# MPU6050.net
KiCad netlist of a schematic drawn in Altium Designer
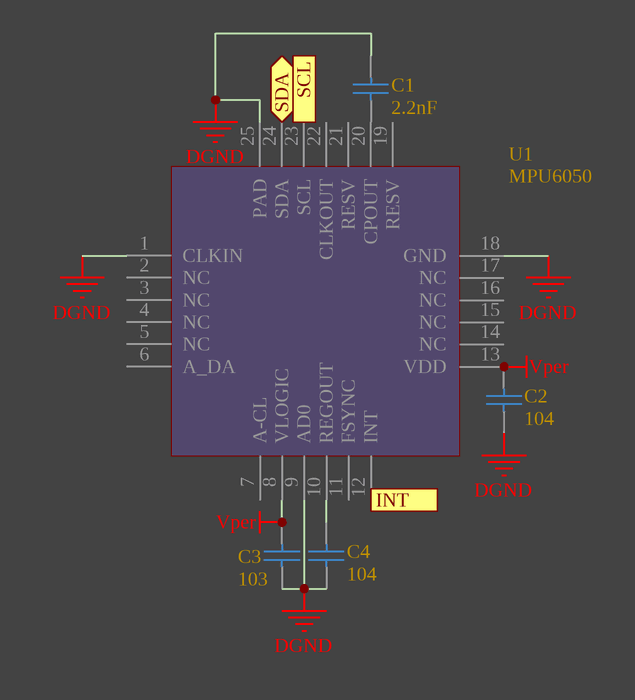
[diagram p0: MPU6050.SchDoc]

(export (version "E")
  (design (tool "Eeschema 10.0.6"))
  (components
    (comp (ref "C1")
      (value "2.2nF")
      (footprint "C0402")
      (description "Capacitor")
      (fields (field (name "PUBLISHER") "Altium Limited"))
      (libsource (lib "iMag") (part "电容"))
    )
    (comp (ref "C2")
      (value "104")
      (footprint "C0402")
      (description "Capacitor")
      (fields (field (name "PUBLISHER") "Altium Limited"))
      (libsource (lib "iMag") (part "电容"))
    )
    (comp (ref "C3")
      (value "103")
      (footprint "C0402")
      (description "Capacitor")
      (fields (field (name "PUBLISHER") "Altium Limited"))
      (libsource (lib "iMag") (part "电容"))
    )
    (comp (ref "C4")
      (value "104")
      (footprint "C0402")
      (description "Capacitor")
      (fields (field (name "PUBLISHER") "Altium Limited"))
      (libsource (lib "iMag") (part "电容"))
    )
    (comp (ref "U1") (value "MPU6050") (footprint "QFN-24_4x4x05P") (libsource (lib "iMag") (part "MPU6050")))
  )
  (nets
    (net (code "1") (name "/INT") (class "Default")
      (node (ref "U1") (pin "12") (pinfunction "INT_12") (pintype "passive"))
    )
    (net (code "2") (name "/SCL") (class "Default")
      (node (ref "U1") (pin "23") (pinfunction "SCL_23") (pintype "passive"))
    )
    (net (code "3") (name "/SDA") (class "Default")
      (node (ref "U1") (pin "24") (pinfunction "SDA_24") (pintype "passive"))
    )
    (net (code "4") (name "DGND") (class "Default")
      (node (ref "C1") (pin "2") (pinfunction "2_2") (pintype "passive"))
      (node (ref "C2") (pin "1") (pinfunction "1_1") (pintype "passive"))
      (node (ref "C3") (pin "1") (pinfunction "1_1") (pintype "passive"))
      (node (ref "C4") (pin "1") (pinfunction "1_1") (pintype "passive"))
      (node (ref "U1") (pin "1") (pinfunction "CLKIN_1") (pintype "passive"))
      (node (ref "U1") (pin "18") (pinfunction "GND_18") (pintype "passive"))
      (node (ref "U1") (pin "25") (pinfunction "PAD_25") (pintype "passive"))
      (node (ref "U1") (pin "9") (pinfunction "AD0_9") (pintype "passive"))
    )
    (net (code "5") (name "Net-(U1-CPOUT)") (class "Default")
      (node (ref "C1") (pin "1") (pinfunction "1_1") (pintype "passive"))
      (node (ref "U1") (pin "20") (pinfunction "CPOUT_20") (pintype "passive"))
    )
    (net (code "6") (name "Net-(U1-REGOUT)") (class "Default")
      (node (ref "C4") (pin "2") (pinfunction "2_2") (pintype "passive"))
      (node (ref "U1") (pin "10") (pinfunction "REGOUT_10") (pintype "passive"))
    )
    (net (code "7") (name "Vper") (class "Default")
      (node (ref "C2") (pin "2") (pinfunction "2_2") (pintype "passive"))
      (node (ref "C3") (pin "2") (pinfunction "2_2") (pintype "passive"))
      (node (ref "U1") (pin "13") (pinfunction "VDD_13") (pintype "passive"))
      (node (ref "U1") (pin "8") (pinfunction "VLOGIC_8") (pintype "passive"))
    )
    (net (code "8") (name "unconnected-(U1-A-CL-Pad7)") (class "Default")
      (node (ref "U1") (pin "7") (pinfunction "A-CL_7") (pintype "passive"))
    )
    (net (code "9") (name "unconnected-(U1-A_DA-Pad6)") (class "Default")
      (node (ref "U1") (pin "6") (pinfunction "A_DA_6") (pintype "passive"))
    )
    (net (code "10") (name "unconnected-(U1-CLKOUT-Pad22)") (class "Default")
      (node (ref "U1") (pin "22") (pinfunction "CLKOUT_22") (pintype "passive"))
    )
    (net (code "11") (name "unconnected-(U1-FSYNC-Pad11)") (class "Default")
      (node (ref "U1") (pin "11") (pinfunction "FSYNC_11") (pintype "passive"))
    )
    (net (code "12") (name "unconnected-(U1-NC-Pad2)") (class "Default")
      (node (ref "U1") (pin "2") (pinfunction "NC_2") (pintype "passive"))
    )
    (net (code "13") (name "unconnected-(U1-NC-Pad3)") (class "Default")
      (node (ref "U1") (pin "3") (pinfunction "NC_3") (pintype "passive"))
    )
    (net (code "14") (name "unconnected-(U1-NC-Pad4)") (class "Default")
      (node (ref "U1") (pin "4") (pinfunction "NC_4") (pintype "passive"))
    )
    (net (code "15") (name "unconnected-(U1-NC-Pad5)") (class "Default")
      (node (ref "U1") (pin "5") (pinfunction "NC_5") (pintype "passive"))
    )
    (net (code "16") (name "unconnected-(U1-NC-Pad14)") (class "Default")
      (node (ref "U1") (pin "14") (pinfunction "NC_14") (pintype "passive"))
    )
    (net (code "17") (name "unconnected-(U1-NC-Pad15)") (class "Default")
      (node (ref "U1") (pin "15") (pinfunction "NC_15") (pintype "passive"))
    )
    (net (code "18") (name "unconnected-(U1-NC-Pad16)") (class "Default")
      (node (ref "U1") (pin "16") (pinfunction "NC_16") (pintype "passive"))
    )
    (net (code "19") (name "unconnected-(U1-NC-Pad17)") (class "Default")
      (node (ref "U1") (pin "17") (pinfunction "NC_17") (pintype "passive"))
    )
    (net (code "20") (name "unconnected-(U1-RESV-Pad19)") (class "Default")
      (node (ref "U1") (pin "19") (pinfunction "RESV_19") (pintype "passive"))
    )
    (net (code "21") (name "unconnected-(U1-RESV-Pad21)") (class "Default")
      (node (ref "U1") (pin "21") (pinfunction "RESV_21") (pintype "passive"))
    )
  )
)
